# PWMSignalSplitter.net
KiCad netlist of a schematic drawn in Altium Designer
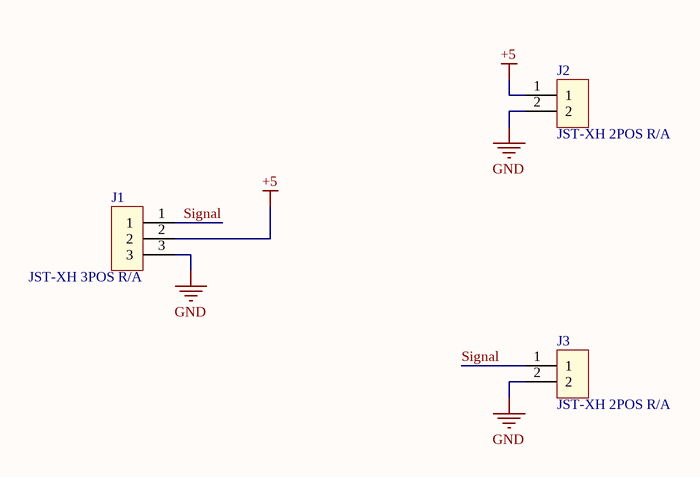
[diagram p0: PWMSignalSplitter.SchDoc]

(export (version "E")
  (design (tool "Eeschema 10.0.6"))
  (components
    (comp (ref "J1")
      (value "JST-XH 3POS R/A")
      (footprint "S3B-XH-A(LF)(SN)")
      (description "JST XH CONN HEADER R/A 3POS 2.5MM")
      (fields (field (name "MANUFACTURER") "JST") (field (name "PART NUMBER") "S3B-XH-A(LF)(SN)"))
      (libsource (lib "MinesROV") (part "S3B-XH-A(LF)(SN)"))
    )
    (comp (ref "J2")
      (value "JST-XH 2POS R/A")
      (footprint "S2B-XH-A(LF)(SN)")
      (description "JST XH CONN HEADER R/A 2POS 2.5MM")
      (fields (field (name "MANUFACTURER") "JST") (field (name "PART NUMBER") "S2B-XH-A(LF)(SN)"))
      (libsource (lib "MinesROV") (part "S2B-XH-A(LF)(SN)"))
    )
    (comp (ref "J3")
      (value "JST-XH 2POS R/A")
      (footprint "S2B-XH-A(LF)(SN)")
      (description "JST XH CONN HEADER R/A 2POS 2.5MM")
      (fields (field (name "MANUFACTURER") "JST") (field (name "PART NUMBER") "S2B-XH-A(LF)(SN)"))
      (libsource (lib "MinesROV") (part "S2B-XH-A(LF)(SN)"))
    )
  )
  (nets
    (net (code "1") (name "+5") (class "Default")
      (node (ref "J1") (pin "2") (pinfunction "2_2") (pintype "passive"))
      (node (ref "J2") (pin "1") (pinfunction "1_1") (pintype "passive"))
    )
    (net (code "2") (name "/Signal") (class "Default")
      (node (ref "J1") (pin "1") (pinfunction "1_1") (pintype "passive"))
      (node (ref "J3") (pin "1") (pinfunction "1_1") (pintype "passive"))
    )
    (net (code "3") (name "GND") (class "Default")
      (node (ref "J1") (pin "3") (pinfunction "3_3") (pintype "passive"))
      (node (ref "J2") (pin "2") (pinfunction "2_2") (pintype "passive"))
      (node (ref "J3") (pin "2") (pinfunction "2_2") (pintype "passive"))
    )
  )
)
